# Display.net
KiCad netlist of a schematic drawn in Altium Designer
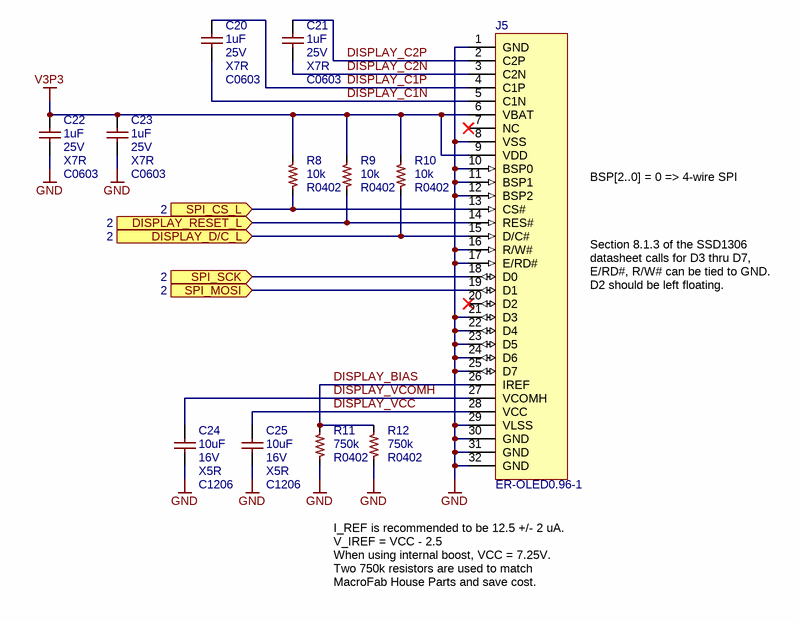
[diagram p0: Display.SchDoc]

(export (version "E")
  (design (tool "Eeschema 10.0.6"))
  (components
    (comp (ref "C20")
      (value "1uF")
      (footprint "C0603")
      (fields
        (field (name "VOLTAGE") "25V")
        (field (name "MATERIAL") "X7R")
        (field (name "Comment") "MF-CAP-0603-1uF")
      )
      (libsource (lib "ReclaimerLabs") (part "CAPACITOR_NP"))
    )
    (comp (ref "C21")
      (value "1uF")
      (footprint "C0603")
      (fields
        (field (name "VOLTAGE") "25V")
        (field (name "MATERIAL") "X7R")
        (field (name "Comment") "MF-CAP-0603-1uF")
      )
      (libsource (lib "ReclaimerLabs") (part "CAPACITOR_NP"))
    )
    (comp (ref "C22")
      (value "1uF")
      (footprint "C0603")
      (fields
        (field (name "VOLTAGE") "25V")
        (field (name "MATERIAL") "X7R")
        (field (name "Comment") "MF-CAP-0603-1uF")
      )
      (libsource (lib "ReclaimerLabs") (part "CAPACITOR_NP"))
    )
    (comp (ref "C23")
      (value "1uF")
      (footprint "C0603")
      (fields
        (field (name "VOLTAGE") "25V")
        (field (name "MATERIAL") "X7R")
        (field (name "Comment") "MF-CAP-0603-1uF")
      )
      (libsource (lib "ReclaimerLabs") (part "CAPACITOR_NP"))
    )
    (comp (ref "C24")
      (value "10uF")
      (footprint "C1206")
      (fields
        (field (name "VOLTAGE") "16V")
        (field (name "MATERIAL") "X5R")
        (field (name "Comment") "MF-CAP-1206-10uF")
      )
      (libsource (lib "ReclaimerLabs") (part "CAPACITOR_NP"))
    )
    (comp (ref "C25")
      (value "10uF")
      (footprint "C1206")
      (fields
        (field (name "VOLTAGE") "16V")
        (field (name "MATERIAL") "X5R")
        (field (name "Comment") "MF-CAP-1206-10uF")
      )
      (libsource (lib "ReclaimerLabs") (part "CAPACITOR_NP"))
    )
    (comp (ref "J5")
      (value "ER-OLED0.96-1")
      (footprint "SFV30R_Mirrored")
      (fields (field (name "Comment") "SFV30R-3STBE1HLF"))
      (libsource (lib "ReclaimerLabs") (part "ER-OLED0.96-1"))
    )
    (comp (ref "R8")
      (value "10k")
      (footprint "ReclaimerLabs:R0402")
      (fields (field (name "Comment") "MF-RES-0402-10K"))
      (libsource (lib "ReclaimerLabs") (part "RESISTOR"))
    )
    (comp (ref "R9")
      (value "10k")
      (footprint "ReclaimerLabs:R0402")
      (fields (field (name "Comment") "MF-RES-0402-10K"))
      (libsource (lib "ReclaimerLabs") (part "RESISTOR"))
    )
    (comp (ref "R10")
      (value "10k")
      (footprint "ReclaimerLabs:R0402")
      (fields (field (name "Comment") "MF-RES-0402-10K"))
      (libsource (lib "ReclaimerLabs") (part "RESISTOR"))
    )
    (comp (ref "R11")
      (value "750k")
      (footprint "R0402")
      (fields (field (name "Comment") "MF-RES-0402-750K"))
      (libsource (lib "ReclaimerLabs") (part "RESISTOR"))
    )
    (comp (ref "R12")
      (value "750k")
      (footprint "R0402")
      (fields (field (name "Comment") "MF-RES-0402-750K"))
      (libsource (lib "ReclaimerLabs") (part "RESISTOR"))
    )
  )
  (nets
    (net (code "1") (name "/DISPLAY_BIAS") (class "Default")
      (node (ref "J5") (pin "26") (pinfunction "IREF_26") (pintype "passive"))
      (node (ref "R11") (pin "1") (pinfunction "R1_1") (pintype "passive"))
      (node (ref "R12") (pin "1") (pinfunction "R1_1") (pintype "passive"))
    )
    (net (code "2") (name "/DISPLAY_C1N") (class "Default")
      (node (ref "C20") (pin "2") (pinfunction "C2_2") (pintype "passive"))
      (node (ref "J5") (pin "5") (pinfunction "C1N_5") (pintype "passive"))
    )
    (net (code "3") (name "/DISPLAY_C1P") (class "Default")
      (node (ref "C20") (pin "1") (pinfunction "C1_1") (pintype "passive"))
      (node (ref "J5") (pin "4") (pinfunction "C1P_4") (pintype "passive"))
    )
    (net (code "4") (name "/DISPLAY_C2N") (class "Default")
      (node (ref "C21") (pin "2") (pinfunction "C2_2") (pintype "passive"))
      (node (ref "J5") (pin "3") (pinfunction "C2N_3") (pintype "passive"))
    )
    (net (code "5") (name "/DISPLAY_C2P") (class "Default")
      (node (ref "C21") (pin "1") (pinfunction "C1_1") (pintype "passive"))
      (node (ref "J5") (pin "2") (pinfunction "C2P_2") (pintype "passive"))
    )
    (net (code "6") (name "/DISPLAY_D{slash}C_L") (class "Default")
      (node (ref "J5") (pin "15") (pinfunction "D/C#_15") (pintype "input"))
      (node (ref "R10") (pin "2") (pinfunction "R2_2") (pintype "passive"))
    )
    (net (code "7") (name "/DISPLAY_RESET_L") (class "Default")
      (node (ref "J5") (pin "14") (pinfunction "RES#_14") (pintype "input"))
      (node (ref "R9") (pin "2") (pinfunction "R2_2") (pintype "passive"))
    )
    (net (code "8") (name "/DISPLAY_VCC") (class "Default")
      (node (ref "C25") (pin "1") (pinfunction "C1_1") (pintype "passive"))
      (node (ref "J5") (pin "28") (pinfunction "VCC_28") (pintype "power_in"))
    )
    (net (code "9") (name "/DISPLAY_VCOMH") (class "Default")
      (node (ref "C24") (pin "1") (pinfunction "C1_1") (pintype "passive"))
      (node (ref "J5") (pin "27") (pinfunction "VCOMH_27") (pintype "power_in"))
    )
    (net (code "10") (name "/SPI_CS_L") (class "Default")
      (node (ref "J5") (pin "13") (pinfunction "CS#_13") (pintype "input"))
      (node (ref "R8") (pin "2") (pinfunction "R2_2") (pintype "passive"))
    )
    (net (code "11") (name "/SPI_MOSI") (class "Default")
      (node (ref "J5") (pin "19") (pinfunction "D1_19") (pintype "bidirectional"))
    )
    (net (code "12") (name "/SPI_SCK") (class "Default")
      (node (ref "J5") (pin "18") (pinfunction "D0_18") (pintype "bidirectional"))
    )
    (net (code "13") (name "GND") (class "Default")
      (node (ref "C22") (pin "2") (pinfunction "C2_2") (pintype "passive"))
      (node (ref "C23") (pin "2") (pinfunction "C2_2") (pintype "passive"))
      (node (ref "C24") (pin "2") (pinfunction "C2_2") (pintype "passive"))
      (node (ref "C25") (pin "2") (pinfunction "C2_2") (pintype "passive"))
      (node (ref "J5") (pin "1") (pinfunction "GND_1") (pintype "passive"))
      (node (ref "J5") (pin "10") (pinfunction "BSP0_10") (pintype "input"))
      (node (ref "J5") (pin "11") (pinfunction "BSP1_11") (pintype "input"))
      (node (ref "J5") (pin "12") (pinfunction "BSP2_12") (pintype "input"))
      (node (ref "J5") (pin "16") (pinfunction "R/W#_16") (pintype "input"))
      (node (ref "J5") (pin "17") (pinfunction "E/RD#_17") (pintype "input"))
      (node (ref "J5") (pin "21") (pinfunction "D3_21") (pintype "bidirectional"))
      (node (ref "J5") (pin "22") (pinfunction "D4_22") (pintype "bidirectional"))
      (node (ref "J5") (pin "23") (pinfunction "D5_23") (pintype "bidirectional"))
      (node (ref "J5") (pin "24") (pinfunction "D6_24") (pintype "bidirectional"))
      (node (ref "J5") (pin "25") (pinfunction "D7_25") (pintype "bidirectional"))
      (node (ref "J5") (pin "29") (pinfunction "VLSS_29") (pintype "passive"))
      (node (ref "J5") (pin "30") (pinfunction "GND_30") (pintype "passive"))
      (node (ref "J5") (pin "31") (pinfunction "GND_31") (pintype "passive"))
      (node (ref "J5") (pin "32") (pinfunction "GND_32") (pintype "passive"))
      (node (ref "J5") (pin "8") (pinfunction "VSS_8") (pintype "passive"))
      (node (ref "R11") (pin "2") (pinfunction "R2_2") (pintype "passive"))
      (node (ref "R12") (pin "2") (pinfunction "R2_2") (pintype "passive"))
    )
    (net (code "14") (name "V3P3") (class "Default")
      (node (ref "C22") (pin "1") (pinfunction "C1_1") (pintype "passive"))
      (node (ref "C23") (pin "1") (pinfunction "C1_1") (pintype "passive"))
      (node (ref "J5") (pin "6") (pinfunction "VBAT_6") (pintype "power_in"))
      (node (ref "J5") (pin "9") (pinfunction "VDD_9") (pintype "power_in"))
      (node (ref "R10") (pin "1") (pinfunction "R1_1") (pintype "passive"))
      (node (ref "R8") (pin "1") (pinfunction "R1_1") (pintype "passive"))
      (node (ref "R9") (pin "1") (pinfunction "R1_1") (pintype "passive"))
    )
    (net (code "15") (name "unconnected-(J5-D2-Pad20)") (class "Default")
      (node (ref "J5") (pin "20") (pinfunction "D2_20") (pintype "bidirectional+no_connect"))
    )
    (net (code "16") (name "unconnected-(J5-NC-Pad7)") (class "Default")
      (node (ref "J5") (pin "7") (pinfunction "NC_7") (pintype "passive+no_connect"))
    )
  )
)
